# QSPI.net
KiCad netlist of a schematic drawn in Altium Designer
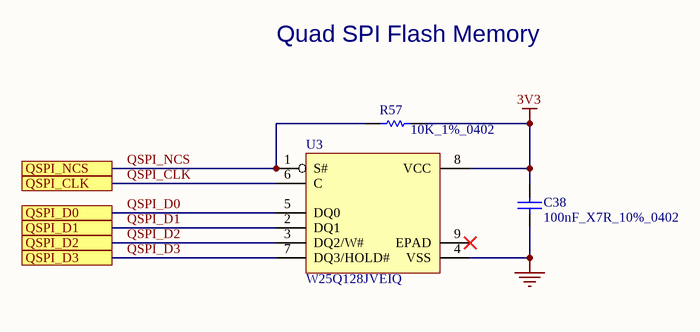
[diagram p0: QSPI.SchDoc]

(export (version "E")
  (design (tool "Eeschema 10.0.6"))
  (components
    (comp (ref "C38")
      (value "100nF_X7R_10%_0402")
      (footprint "0402C")
      (description "Capacitor,100nF,16V,X7R,10%,0402,YAGEO")
      (libsource (lib "MCD_TOOLS") (part "Cap_100nF_X7R_10%_0402"))
    )
    (comp (ref "R57")
      (value "10K_1%_0402")
      (footprint "0402R")
      (description "Resistor,10K,0402,1%,YAGEO")
      (libsource (lib "MCD_TOOLS") (part "Res_10K_1%_0402"))
    )
    (comp (ref "U3")
      (value "W25Q128JVEIQ")
      (footprint "W-PDFN-8_8X6_P127")
      (description "128Mb, 3V, Multiple I/O Serial Flash Memory, Quad/Dual")
      (libsource (lib "Mb1191") (part "MT25QL128ABA1EW9-0SIT"))
    )
  )
  (nets
    (net (code "1") (name "/QSPI_CLK") (class "Default")
      (node (ref "U3") (pin "6") (pinfunction "C_6") (pintype "passive"))
    )
    (net (code "2") (name "/QSPI_D0") (class "Default")
      (node (ref "U3") (pin "5") (pinfunction "DQ0_5") (pintype "passive"))
    )
    (net (code "3") (name "/QSPI_D1") (class "Default")
      (node (ref "U3") (pin "2") (pinfunction "DQ1_2") (pintype "passive"))
    )
    (net (code "4") (name "/QSPI_D2") (class "Default")
      (node (ref "U3") (pin "3") (pinfunction "DQ2/W#_3") (pintype "passive"))
    )
    (net (code "5") (name "/QSPI_D3") (class "Default")
      (node (ref "U3") (pin "7") (pinfunction "DQ3/HOLD#_7") (pintype "passive"))
    )
    (net (code "6") (name "/QSPI_NCS") (class "Default")
      (node (ref "R57") (pin "1") (pinfunction "1_1") (pintype "passive"))
      (node (ref "U3") (pin "1") (pinfunction "S#_1") (pintype "passive"))
    )
    (net (code "7") (name "3V3") (class "Default")
      (node (ref "C38") (pin "2") (pinfunction "2_2") (pintype "passive"))
      (node (ref "R57") (pin "2") (pinfunction "2_2") (pintype "passive"))
      (node (ref "U3") (pin "8") (pinfunction "VCC_8") (pintype "passive"))
    )
    (net (code "8") (name "GND") (class "Default")
      (node (ref "C38") (pin "1") (pinfunction "1_1") (pintype "passive"))
      (node (ref "U3") (pin "4") (pinfunction "VSS_4") (pintype "passive"))
    )
    (net (code "9") (name "unconnected-(U3-EPAD-Pad9)") (class "Default")
      (node (ref "U3") (pin "9") (pinfunction "EPAD_9") (pintype "passive+no_connect"))
    )
  )
)
